# vco_main.net
KiCad netlist of a schematic drawn in EAGLE
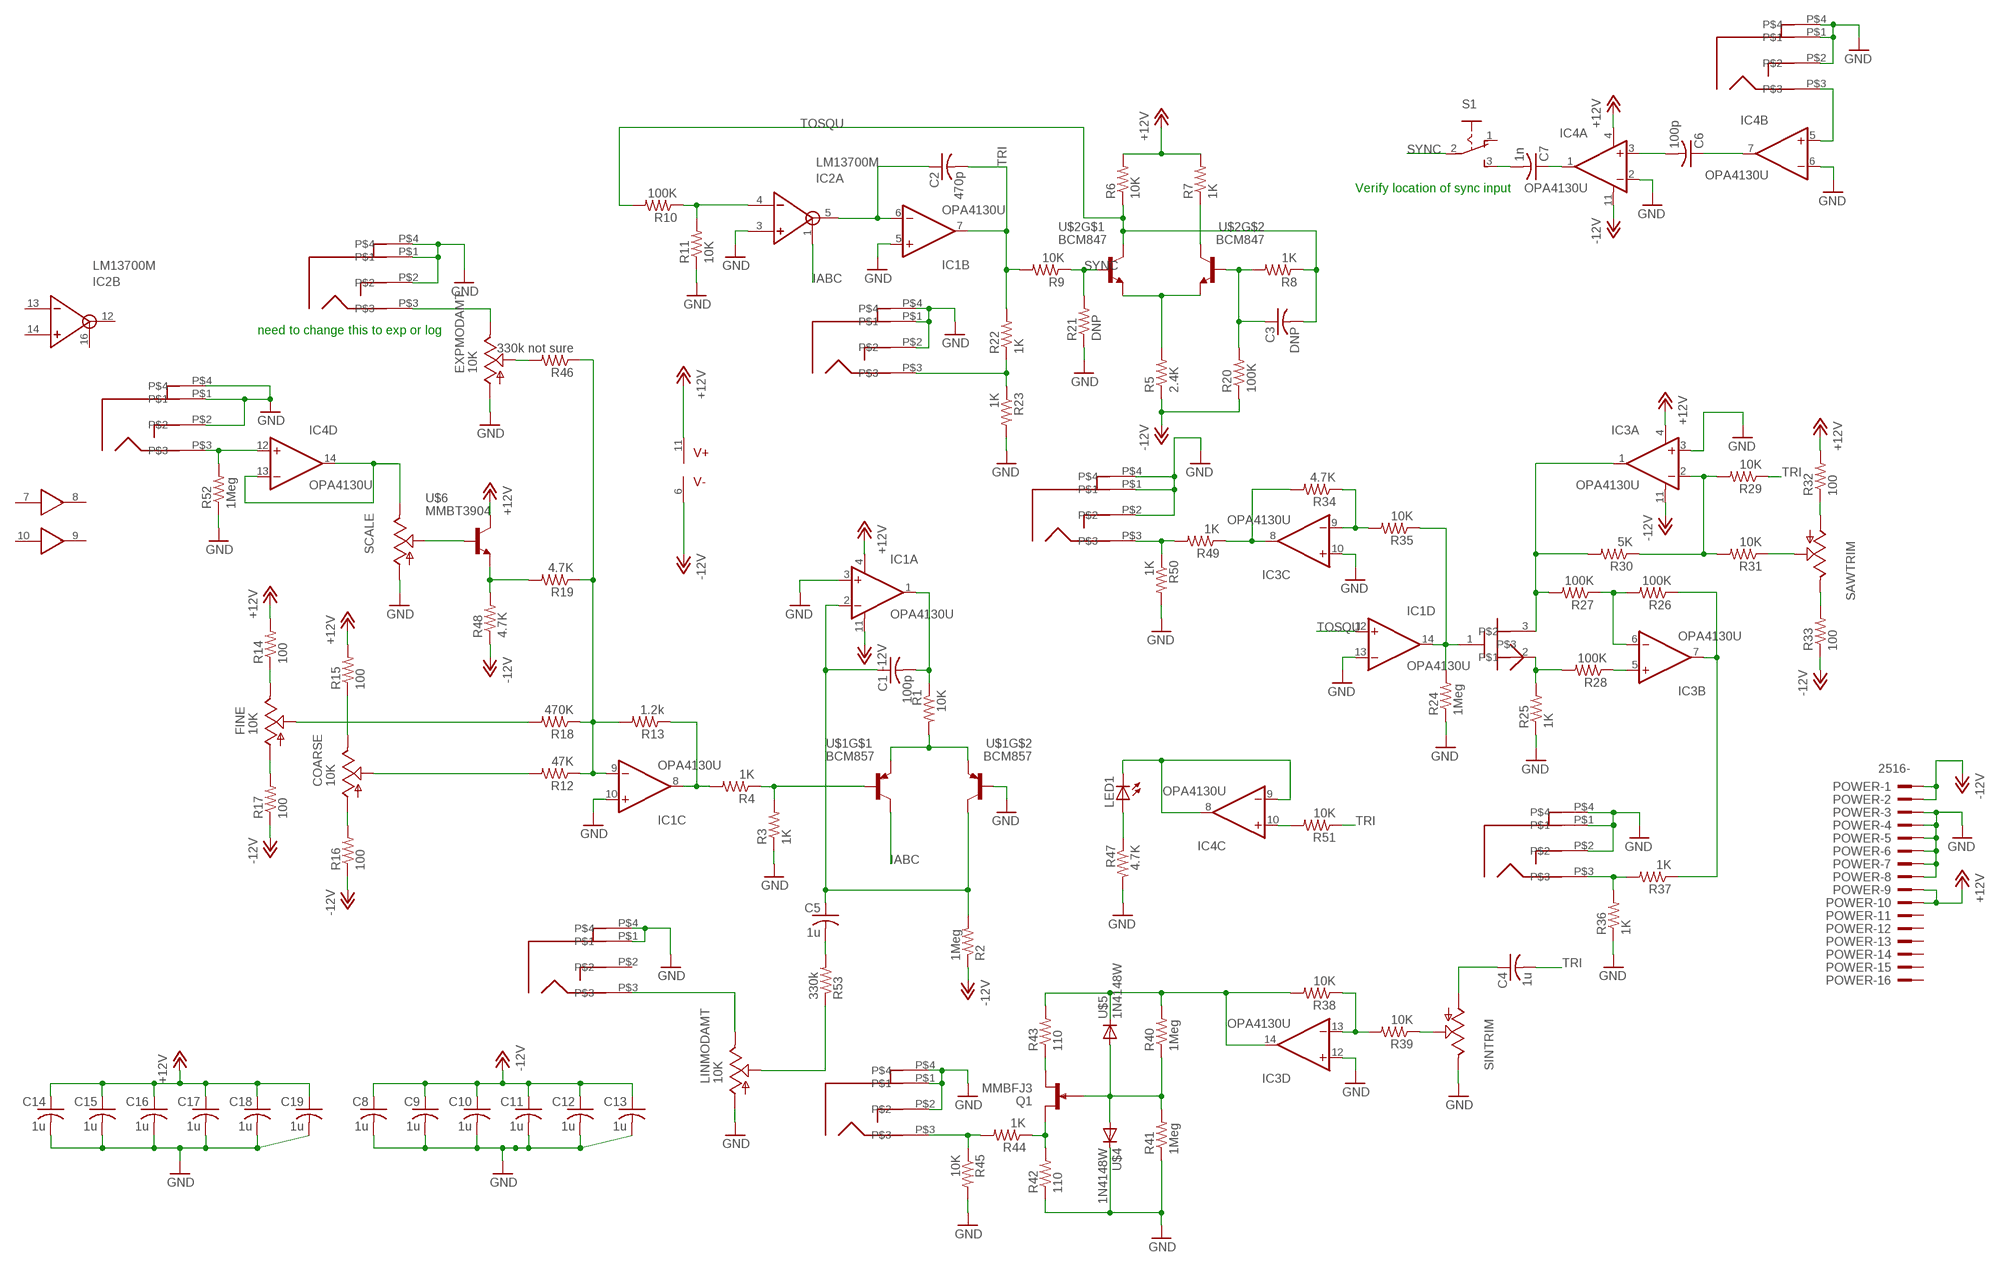
[diagram p0: schematic, sheet 1]

(export (version "E")
  (design (tool "Eeschema 10.0.6"))
  (components
    (comp (ref "C1")
      (value "100p")
      (footprint "eagle-import:C0603")
      (libsource (lib "eagle-import") (part "C-USC0603"))
    )
    (comp (ref "C2")
      (value "470p")
      (footprint "eagle-import:C0603")
      (libsource (lib "eagle-import") (part "C-USC0603"))
    )
    (comp (ref "C3")
      (value "DNP")
      (footprint "eagle-import:C0603")
      (libsource (lib "eagle-import") (part "C-USC0603"))
    )
    (comp (ref "C4")
      (value "1u")
      (footprint "eagle-import:C0603")
      (libsource (lib "eagle-import") (part "C-USC0603"))
    )
    (comp (ref "C5")
      (value "1u")
      (footprint "eagle-import:C0603")
      (libsource (lib "eagle-import") (part "C-USC0603"))
    )
    (comp (ref "C6")
      (value "100p")
      (footprint "eagle-import:C0603")
      (libsource (lib "eagle-import") (part "C-USC0603"))
    )
    (comp (ref "C7")
      (value "1n")
      (footprint "eagle-import:C0603")
      (libsource (lib "eagle-import") (part "C-USC0603"))
    )
    (comp (ref "C8")
      (value "1u")
      (footprint "eagle-import:C0603")
      (libsource (lib "eagle-import") (part "C-USC0603"))
    )
    (comp (ref "C9")
      (value "1u")
      (footprint "eagle-import:C0603")
      (libsource (lib "eagle-import") (part "C-USC0603"))
    )
    (comp (ref "C10")
      (value "1u")
      (footprint "eagle-import:C0603")
      (libsource (lib "eagle-import") (part "C-USC0603"))
    )
    (comp (ref "C11")
      (value "1u")
      (footprint "eagle-import:C0603")
      (libsource (lib "eagle-import") (part "C-USC0603"))
    )
    (comp (ref "C12")
      (value "1u")
      (footprint "eagle-import:C0603")
      (libsource (lib "eagle-import") (part "C-USC0603"))
    )
    (comp (ref "C13")
      (value "1u")
      (footprint "eagle-import:C0603")
      (libsource (lib "eagle-import") (part "C-USC0603"))
    )
    (comp (ref "C14")
      (value "1u")
      (footprint "eagle-import:C0603")
      (libsource (lib "eagle-import") (part "C-USC0603"))
    )
    (comp (ref "C15")
      (value "1u")
      (footprint "eagle-import:C0603")
      (libsource (lib "eagle-import") (part "C-USC0603"))
    )
    (comp (ref "C16")
      (value "1u")
      (footprint "eagle-import:C0603")
      (libsource (lib "eagle-import") (part "C-USC0603"))
    )
    (comp (ref "C17")
      (value "1u")
      (footprint "eagle-import:C0603")
      (libsource (lib "eagle-import") (part "C-USC0603"))
    )
    (comp (ref "C18")
      (value "1u")
      (footprint "eagle-import:C0603")
      (libsource (lib "eagle-import") (part "C-USC0603"))
    )
    (comp (ref "C19")
      (value "1u")
      (footprint "eagle-import:C0603")
      (libsource (lib "eagle-import") (part "C-USC0603"))
    )
    (comp (ref "COARSE")
      (value "10K")
      (footprint "eagle-import:EVUFXJ")
      (libsource (lib "eagle-import") (part "US-EVUF2J"))
    )
    (comp (ref "EXPMOD")
      (value "PJ301BM")
      (footprint "eagle-import:PJ301BM")
      (libsource (lib "eagle-import") (part "PJ301BM"))
    )
    (comp (ref "EXPMODAMT")
      (value "10K")
      (footprint "eagle-import:EVUFXJ")
      (libsource (lib "eagle-import") (part "US-EVUF2J"))
    )
    (comp (ref "FINE")
      (value "10K")
      (footprint "eagle-import:EVUFXJ")
      (libsource (lib "eagle-import") (part "US-EVUF2J"))
    )
    (comp (ref "IC1")
      (value "OPA4130U")
      (footprint "eagle-import:SO14")
      (fields (field (name "MF") "TEXAS INSTRUMENTS") (field (name "MPN") "OPA4130UA"))
      (libsource (lib "eagle-import") (part "OPA4130U"))
    )
    (comp (ref "IC2")
      (value "LM13700M")
      (footprint "eagle-import:SO16")
      (libsource (lib "eagle-import") (part "LM13700M"))
    )
    (comp (ref "IC3")
      (value "OPA4130U")
      (footprint "eagle-import:SO14")
      (fields (field (name "MF") "TEXAS INSTRUMENTS") (field (name "MPN") "OPA4130UA"))
      (libsource (lib "eagle-import") (part "OPA4130U"))
    )
    (comp (ref "IC4")
      (value "OPA4130U")
      (footprint "eagle-import:SO14")
      (fields (field (name "MF") "TEXAS INSTRUMENTS") (field (name "MPN") "OPA4130UA"))
      (libsource (lib "eagle-import") (part "OPA4130U"))
    )
    (comp (ref "LED1")
      (value "LED5MM")
      (footprint "eagle-import:LED5MM")
      (libsource (lib "eagle-import") (part "LED5MM"))
    )
    (comp (ref "LINMOD")
      (value "PJ301BM")
      (footprint "eagle-import:PJ301BM")
      (libsource (lib "eagle-import") (part "PJ301BM"))
    )
    (comp (ref "LINMODAMT")
      (value "10K")
      (footprint "eagle-import:EVUFXJ")
      (libsource (lib "eagle-import") (part "US-EVUF2J"))
    )
    (comp (ref "POWER")
      (value "2516-")
      (footprint "eagle-import:PAK100_2500-16")
      (libsource (lib "eagle-import") (part "2516-"))
    )
    (comp (ref "Q1")
      (value "MMBFJ3")
      (footprint "eagle-import:SOT23")
      (libsource (lib "eagle-import") (part "MMBFJ3"))
    )
    (comp (ref "R1")
      (value "10K")
      (footprint "eagle-import:R0603")
      (libsource (lib "eagle-import") (part "R-US_R0603"))
    )
    (comp (ref "R2")
      (value "1Meg")
      (footprint "eagle-import:R0603")
      (libsource (lib "eagle-import") (part "R-US_R0603"))
    )
    (comp (ref "R3")
      (value "1K")
      (footprint "eagle-import:R0603")
      (libsource (lib "eagle-import") (part "R-US_R0603"))
    )
    (comp (ref "R4")
      (value "1K")
      (footprint "eagle-import:R0603")
      (libsource (lib "eagle-import") (part "R-US_R0603"))
    )
    (comp (ref "R5")
      (value "2.4K")
      (footprint "eagle-import:R0603")
      (libsource (lib "eagle-import") (part "R-US_R0603"))
    )
    (comp (ref "R6")
      (value "10K")
      (footprint "eagle-import:R0603")
      (libsource (lib "eagle-import") (part "R-US_R0603"))
    )
    (comp (ref "R7")
      (value "1K")
      (footprint "eagle-import:R0603")
      (libsource (lib "eagle-import") (part "R-US_R0603"))
    )
    (comp (ref "R8")
      (value "1K")
      (footprint "eagle-import:R0603")
      (libsource (lib "eagle-import") (part "R-US_R0603"))
    )
    (comp (ref "R9")
      (value "10K")
      (footprint "eagle-import:R0603")
      (libsource (lib "eagle-import") (part "R-US_R0603"))
    )
    (comp (ref "R10")
      (value "100K")
      (footprint "eagle-import:R0603")
      (libsource (lib "eagle-import") (part "R-US_R0603"))
    )
    (comp (ref "R11")
      (value "10K")
      (footprint "eagle-import:R0603")
      (libsource (lib "eagle-import") (part "R-US_R0603"))
    )
    (comp (ref "R12")
      (value "47K")
      (footprint "eagle-import:R0603")
      (libsource (lib "eagle-import") (part "R-US_R0603"))
    )
    (comp (ref "R13")
      (value "1.2k")
      (footprint "eagle-import:R0603")
      (libsource (lib "eagle-import") (part "R-US_R0603"))
    )
    (comp (ref "R14")
      (value "100")
      (footprint "eagle-import:R0603")
      (libsource (lib "eagle-import") (part "R-US_R0603"))
    )
    (comp (ref "R15")
      (value "100")
      (footprint "eagle-import:R0603")
      (libsource (lib "eagle-import") (part "R-US_R0603"))
    )
    (comp (ref "R16")
      (value "100")
      (footprint "eagle-import:R0603")
      (libsource (lib "eagle-import") (part "R-US_R0603"))
    )
    (comp (ref "R17")
      (value "100")
      (footprint "eagle-import:R0603")
      (libsource (lib "eagle-import") (part "R-US_R0603"))
    )
    (comp (ref "R18")
      (value "470K")
      (footprint "eagle-import:R0603")
      (libsource (lib "eagle-import") (part "R-US_R0603"))
    )
    (comp (ref "R19")
      (value "4.7K")
      (footprint "eagle-import:R0603")
      (libsource (lib "eagle-import") (part "R-US_R0603"))
    )
    (comp (ref "R20")
      (value "100K")
      (footprint "eagle-import:R0603")
      (libsource (lib "eagle-import") (part "R-US_R0603"))
    )
    (comp (ref "R21")
      (value "DNP")
      (footprint "eagle-import:R0603")
      (libsource (lib "eagle-import") (part "R-US_R0603"))
    )
    (comp (ref "R22")
      (value "1K")
      (footprint "eagle-import:R0603")
      (libsource (lib "eagle-import") (part "R-US_R0603"))
    )
    (comp (ref "R23")
      (value "1K")
      (footprint "eagle-import:R0603")
      (libsource (lib "eagle-import") (part "R-US_R0603"))
    )
    (comp (ref "R24")
      (value "1Meg")
      (footprint "eagle-import:R0603")
      (libsource (lib "eagle-import") (part "R-US_R0603"))
    )
    (comp (ref "R25")
      (value "1K")
      (footprint "eagle-import:R0603")
      (libsource (lib "eagle-import") (part "R-US_R0603"))
    )
    (comp (ref "R26")
      (value "100K")
      (footprint "eagle-import:R0603")
      (libsource (lib "eagle-import") (part "R-US_R0603"))
    )
    (comp (ref "R27")
      (value "100K")
      (footprint "eagle-import:R0603")
      (libsource (lib "eagle-import") (part "R-US_R0603"))
    )
    (comp (ref "R28")
      (value "100K")
      (footprint "eagle-import:R0603")
      (libsource (lib "eagle-import") (part "R-US_R0603"))
    )
    (comp (ref "R29")
      (value "10K")
      (footprint "eagle-import:R0603")
      (libsource (lib "eagle-import") (part "R-US_R0603"))
    )
    (comp (ref "R30")
      (value "5K")
      (footprint "eagle-import:R0603")
      (libsource (lib "eagle-import") (part "R-US_R0603"))
    )
    (comp (ref "R31")
      (value "10K")
      (footprint "eagle-import:R0603")
      (libsource (lib "eagle-import") (part "R-US_R0603"))
    )
    (comp (ref "R32")
      (value "100")
      (footprint "eagle-import:R0603")
      (libsource (lib "eagle-import") (part "R-US_R0603"))
    )
    (comp (ref "R33")
      (value "100")
      (footprint "eagle-import:R0603")
      (libsource (lib "eagle-import") (part "R-US_R0603"))
    )
    (comp (ref "R34")
      (value "4.7K")
      (footprint "eagle-import:R0603")
      (libsource (lib "eagle-import") (part "R-US_R0603"))
    )
    (comp (ref "R35")
      (value "10K")
      (footprint "eagle-import:R0603")
      (libsource (lib "eagle-import") (part "R-US_R0603"))
    )
    (comp (ref "R36")
      (value "1K")
      (footprint "eagle-import:R0603")
      (libsource (lib "eagle-import") (part "R-US_R0603"))
    )
    (comp (ref "R37")
      (value "1K")
      (footprint "eagle-import:R0603")
      (libsource (lib "eagle-import") (part "R-US_R0603"))
    )
    (comp (ref "R38")
      (value "10K")
      (footprint "eagle-import:R0603")
      (libsource (lib "eagle-import") (part "R-US_R0603"))
    )
    (comp (ref "R39")
      (value "10K")
      (footprint "eagle-import:R0603")
      (libsource (lib "eagle-import") (part "R-US_R0603"))
    )
    (comp (ref "R40")
      (value "1Meg")
      (footprint "eagle-import:R0603")
      (libsource (lib "eagle-import") (part "R-US_R0603"))
    )
    (comp (ref "R41")
      (value "1Meg")
      (footprint "eagle-import:R0603")
      (libsource (lib "eagle-import") (part "R-US_R0603"))
    )
    (comp (ref "R42")
      (value "110")
      (footprint "eagle-import:R0603")
      (libsource (lib "eagle-import") (part "R-US_R0603"))
    )
    (comp (ref "R43")
      (value "110")
      (footprint "eagle-import:R0603")
      (libsource (lib "eagle-import") (part "R-US_R0603"))
    )
    (comp (ref "R44")
      (value "1K")
      (footprint "eagle-import:R0603")
      (libsource (lib "eagle-import") (part "R-US_R0603"))
    )
    (comp (ref "R45")
      (value "10K")
      (footprint "eagle-import:R0603")
      (libsource (lib "eagle-import") (part "R-US_R0603"))
    )
    (comp (ref "R46")
      (value "330k not sure")
      (footprint "eagle-import:R0603")
      (libsource (lib "eagle-import") (part "R-US_R0603"))
    )
    (comp (ref "R47")
      (value "4.7K")
      (footprint "eagle-import:R0603")
      (libsource (lib "eagle-import") (part "R-US_R0603"))
    )
    (comp (ref "R48")
      (value "4.7K")
      (footprint "eagle-import:R0603")
      (libsource (lib "eagle-import") (part "R-US_R0603"))
    )
    (comp (ref "R49")
      (value "1K")
      (footprint "eagle-import:R0603")
      (libsource (lib "eagle-import") (part "R-US_R0603"))
    )
    (comp (ref "R50")
      (value "1K")
      (footprint "eagle-import:R0603")
      (libsource (lib "eagle-import") (part "R-US_R0603"))
    )
    (comp (ref "R51")
      (value "10K")
      (footprint "eagle-import:R0603")
      (libsource (lib "eagle-import") (part "R-US_R0603"))
    )
    (comp (ref "R52")
      (value "1Meg")
      (footprint "eagle-import:R0603")
      (libsource (lib "eagle-import") (part "R-US_R0603"))
    )
    (comp (ref "R53")
      (value "330k")
      (footprint "eagle-import:R0603")
      (libsource (lib "eagle-import") (part "R-US_R0603"))
    )
    (comp (ref "S1")
      (value "255SB")
      (footprint "eagle-import:255SB")
      (libsource (lib "eagle-import") (part "255SB"))
    )
    (comp (ref "SAW")
      (value "PJ301BM")
      (footprint "eagle-import:PJ301BM")
      (libsource (lib "eagle-import") (part "PJ301BM"))
    )
    (comp (ref "SAWTRIM")
      (value "TRIM_US-B64Y")
      (footprint "eagle-import:B64Y")
      (libsource (lib "eagle-import") (part "TRIM_US-B64Y"))
    )
    (comp (ref "SCALE")
      (value "TRIM_US-B64Y")
      (footprint "eagle-import:B64Y")
      (libsource (lib "eagle-import") (part "TRIM_US-B64Y"))
    )
    (comp (ref "SIN")
      (value "PJ301BM")
      (footprint "eagle-import:PJ301BM")
      (libsource (lib "eagle-import") (part "PJ301BM"))
    )
    (comp (ref "SINTRIM")
      (value "TRIM_US-B64Y")
      (footprint "eagle-import:B64Y")
      (libsource (lib "eagle-import") (part "TRIM_US-B64Y"))
    )
    (comp (ref "SQUARE")
      (value "PJ301BM")
      (footprint "eagle-import:PJ301BM")
      (libsource (lib "eagle-import") (part "PJ301BM"))
    )
    (comp (ref "SYNC")
      (value "PJ301BM")
      (footprint "eagle-import:PJ301BM")
      (libsource (lib "eagle-import") (part "PJ301BM"))
    )
    (comp (ref "TRIOUT")
      (value "PJ301BM")
      (footprint "eagle-import:PJ301BM")
      (libsource (lib "eagle-import") (part "PJ301BM"))
    )
    (comp (ref "U$1")
      (value "BCM857")
      (footprint "eagle-import:SOT457R_PHILIPS")
      (libsource (lib "eagle-import") (part "BCM857"))
    )
    (comp (ref "U$2")
      (value "BCM847")
      (footprint "eagle-import:SOT457R_PHILIPS")
      (libsource (lib "eagle-import") (part "BCM847"))
    )
    (comp (ref "U$3")
      (value "2N7000")
      (footprint "eagle-import:SOT23")
      (libsource (lib "eagle-import") (part "2N7000"))
    )
    (comp (ref "U$4")
      (value "1N4148W")
      (footprint "eagle-import:SOD123")
      (libsource (lib "eagle-import") (part "1N4148W"))
    )
    (comp (ref "U$5")
      (value "1N4148W")
      (footprint "eagle-import:SOD123")
      (libsource (lib "eagle-import") (part "1N4148W"))
    )
    (comp (ref "U$6")
      (value "MMBT3904")
      (footprint "eagle-import:SOT23")
      (libsource (lib "eagle-import") (part "MMBT3904"))
    )
    (comp (ref "VPEROCT")
      (value "PJ301BM")
      (footprint "eagle-import:PJ301BM")
      (libsource (lib "eagle-import") (part "PJ301BM"))
    )
  )
  (nets
    (net (code "1") (name "+12V") (class "Default")
      (node (ref "C14") (pin "1") (pinfunction "1_1") (pintype "passive"))
      (node (ref "C15") (pin "1") (pinfunction "1_1") (pintype "passive"))
      (node (ref "C16") (pin "1") (pinfunction "1_1") (pintype "passive"))
      (node (ref "C17") (pin "1") (pinfunction "1_1") (pintype "passive"))
      (node (ref "C18") (pin "1") (pinfunction "1_1") (pintype "passive"))
      (node (ref "C19") (pin "1") (pinfunction "1_1") (pintype "passive"))
      (node (ref "IC1") (pin "4") (pinfunction "V+_4") (pintype "power_in"))
      (node (ref "IC2") (pin "11") (pinfunction "V+_11") (pintype "bidirectional"))
      (node (ref "IC3") (pin "4") (pinfunction "V+_4") (pintype "power_in"))
      (node (ref "IC4") (pin "4") (pinfunction "V+_4") (pintype "power_in"))
      (node (ref "POWER") (pin "10") (pinfunction "KL_10") (pintype "passive"))
      (node (ref "POWER") (pin "9") (pinfunction "KL_9") (pintype "passive"))
      (node (ref "R14") (pin "2") (pinfunction "2_2") (pintype "passive"))
      (node (ref "R15") (pin "2") (pinfunction "2_2") (pintype "passive"))
      (node (ref "R32") (pin "2") (pinfunction "2_2") (pintype "passive"))
      (node (ref "R6") (pin "2") (pinfunction "2_2") (pintype "passive"))
      (node (ref "R7") (pin "2") (pinfunction "2_2") (pintype "passive"))
      (node (ref "U$6") (pin "3") (pinfunction "C_3") (pintype "passive"))
    )
    (net (code "2") (name "-12V") (class "Default")
      (node (ref "C10") (pin "1") (pinfunction "1_1") (pintype "passive"))
      (node (ref "C11") (pin "1") (pinfunction "1_1") (pintype "passive"))
      (node (ref "C12") (pin "1") (pinfunction "1_1") (pintype "passive"))
      (node (ref "C13") (pin "1") (pinfunction "1_1") (pintype "passive"))
      (node (ref "C8") (pin "1") (pinfunction "1_1") (pintype "passive"))
      (node (ref "C9") (pin "1") (pinfunction "1_1") (pintype "passive"))
      (node (ref "IC1") (pin "11") (pinfunction "V-_11") (pintype "power_in"))
      (node (ref "IC2") (pin "6") (pinfunction "V-_6") (pintype "bidirectional"))
      (node (ref "IC3") (pin "11") (pinfunction "V-_11") (pintype "power_in"))
      (node (ref "IC4") (pin "11") (pinfunction "V-_11") (pintype "power_in"))
      (node (ref "POWER") (pin "1") (pinfunction "KL_1") (pintype "passive"))
      (node (ref "POWER") (pin "2") (pinfunction "KL_2") (pintype "passive"))
      (node (ref "R16") (pin "1") (pinfunction "1_1") (pintype "passive"))
      (node (ref "R17") (pin "1") (pinfunction "1_1") (pintype "passive"))
      (node (ref "R2") (pin "1") (pinfunction "1_1") (pintype "passive"))
      (node (ref "R20") (pin "1") (pinfunction "1_1") (pintype "passive"))
      (node (ref "R33") (pin "1") (pinfunction "1_1") (pintype "passive"))
      (node (ref "R48") (pin "1") (pinfunction "1_1") (pintype "passive"))
      (node (ref "R5") (pin "1") (pinfunction "1_1") (pintype "passive"))
    )
    (net (code "3") (name "/IABC") (class "Default")
      (node (ref "IC2") (pin "1") (pinfunction "IABC_1") (pintype "bidirectional"))
      (node (ref "U$1") (pin "6") (pinfunction "C_6") (pintype "passive"))
    )
    (net (code "4") (name "/SYNC") (class "Default")
      (node (ref "R21") (pin "2") (pinfunction "2_2") (pintype "passive"))
      (node (ref "R9") (pin "1") (pinfunction "1_1") (pintype "passive"))
      (node (ref "S1") (pin "2") (pinfunction "P_2") (pintype "passive"))
      (node (ref "U$2") (pin "2") (pinfunction "B_2") (pintype "passive"))
    )
    (net (code "5") (name "/TOSQU") (class "Default")
      (node (ref "C3") (pin "2") (pinfunction "2_2") (pintype "passive"))
      (node (ref "IC1") (pin "12") (pinfunction "+IN_12") (pintype "input"))
      (node (ref "R10") (pin "2") (pinfunction "2_2") (pintype "passive"))
      (node (ref "R6") (pin "1") (pinfunction "1_1") (pintype "passive"))
      (node (ref "R8") (pin "1") (pinfunction "1_1") (pintype "passive"))
      (node (ref "U$2") (pin "6") (pinfunction "C_6") (pintype "passive"))
    )
    (net (code "6") (name "/TRI") (class "Default")
      (node (ref "C2") (pin "2") (pinfunction "2_2") (pintype "passive"))
      (node (ref "C4") (pin "2") (pinfunction "2_2") (pintype "passive"))
      (node (ref "IC1") (pin "7") (pinfunction "OUT_7") (pintype "output"))
      (node (ref "R22") (pin "2") (pinfunction "2_2") (pintype "passive"))
      (node (ref "R29") (pin "1") (pinfunction "1_1") (pintype "passive"))
      (node (ref "R51") (pin "1") (pinfunction "1_1") (pintype "passive"))
      (node (ref "R9") (pin "2") (pinfunction "2_2") (pintype "passive"))
    )
    (net (code "7") (name "GND") (class "Default")
      (node (ref "C10") (pin "2") (pinfunction "2_2") (pintype "passive"))
      (node (ref "C11") (pin "2") (pinfunction "2_2") (pintype "passive"))
      (node (ref "C12") (pin "2") (pinfunction "2_2") (pintype "passive"))
      (node (ref "C13") (pin "2") (pinfunction "2_2") (pintype "passive"))
      (node (ref "C14") (pin "2") (pinfunction "2_2") (pintype "passive"))
      (node (ref "C15") (pin "2") (pinfunction "2_2") (pintype "passive"))
      (node (ref "C16") (pin "2") (pinfunction "2_2") (pintype "passive"))
      (node (ref "C17") (pin "2") (pinfunction "2_2") (pintype "passive"))
      (node (ref "C18") (pin "2") (pinfunction "2_2") (pintype "passive"))
      (node (ref "C19") (pin "2") (pinfunction "2_2") (pintype "passive"))
      (node (ref "C8") (pin "2") (pinfunction "2_2") (pintype "passive"))
      (node (ref "C9") (pin "2") (pinfunction "2_2") (pintype "passive"))
      (node (ref "EXPMOD") (pin "P$1") (pinfunction "P$1_P$1") (pintype "bidirectional"))
      (node (ref "EXPMOD") (pin "P$2") (pinfunction "P$2_P$2") (pintype "bidirectional"))
      (node (ref "EXPMOD") (pin "P$4") (pinfunction "P$4_P$4") (pintype "bidirectional"))
      (node (ref "EXPMODAMT") (pin "1") (pinfunction "A_1") (pintype "passive"))
      (node (ref "IC1") (pin "10") (pinfunction "+IN_10") (pintype "input"))
      (node (ref "IC1") (pin "13") (pinfunction "-IN_13") (pintype "input"))
      (node (ref "IC1") (pin "3") (pinfunction "+IN_3") (pintype "input"))
      (node (ref "IC1") (pin "5") (pinfunction "+IN_5") (pintype "input"))
      (node (ref "IC2") (pin "3") (pinfunction "+IN_3") (pintype "bidirectional"))
      (node (ref "IC3") (pin "10") (pinfunction "+IN_10") (pintype "input"))
      (node (ref "IC3") (pin "12") (pinfunction "+IN_12") (pintype "input"))
      (node (ref "IC3") (pin "3") (pinfunction "+IN_3") (pintype "input"))
      (node (ref "IC4") (pin "2") (pinfunction "-IN_2") (pintype "input"))
      (node (ref "IC4") (pin "6") (pinfunction "-IN_6") (pintype "input"))
      (node (ref "LINMOD") (pin "P$1") (pinfunction "P$1_P$1") (pintype "bidirectional"))
      (node (ref "LINMOD") (pin "P$4") (pinfunction "P$4_P$4") (pintype "bidirectional"))
      (node (ref "LINMODAMT") (pin "1") (pinfunction "A_1") (pintype "passive"))
      (node (ref "POWER") (pin "3") (pinfunction "KL_3") (pintype "passive"))
      (node (ref "POWER") (pin "4") (pinfunction "KL_4") (pintype "passive"))
      (node (ref "POWER") (pin "5") (pinfunction "KL_5") (pintype "passive"))
      (node (ref "POWER") (pin "6") (pinfunction "KL_6") (pintype "passive"))
      (node (ref "POWER") (pin "7") (pinfunction "KL_7") (pintype "passive"))
      (node (ref "POWER") (pin "8") (pinfunction "KL_8") (pintype "passive"))
      (node (ref "R11") (pin "1") (pinfunction "1_1") (pintype "passive"))
      (node (ref "R21") (pin "1") (pinfunction "1_1") (pintype "passive"))
      (node (ref "R23") (pin "2") (pinfunction "2_2") (pintype "passive"))
      (node (ref "R24") (pin "1") (pinfunction "1_1") (pintype "passive"))
      (node (ref "R25") (pin "1") (pinfunction "1_1") (pintype "passive"))
      (node (ref "R3") (pin "1") (pinfunction "1_1") (pintype "passive"))
      (node (ref "R36") (pin "1") (pinfunction "1_1") (pintype "passive"))
      (node (ref "R41") (pin "1") (pinfunction "1_1") (pintype "passive"))
      (node (ref "R42") (pin "1") (pinfunction "1_1") (pintype "passive"))
      (node (ref "R45") (pin "2") (pinfunction "2_2") (pintype "passive"))
      (node (ref "R47") (pin "2") (pinfunction "2_2") (pintype "passive"))
      (node (ref "R50") (pin "2") (pinfunction "2_2") (pintype "passive"))
      (node (ref "R52") (pin "1") (pinfunction "1_1") (pintype "passive"))
      (node (ref "SAW") (pin "P$1") (pinfunction "P$1_P$1") (pintype "bidirectional"))
      (node (ref "SAW") (pin "P$2") (pinfunction "P$2_P$2") (pintype "bidirectional"))
      (node (ref "SAW") (pin "P$4") (pinfunction "P$4_P$4") (pintype "bidirectional"))
      (node (ref "SCALE") (pin "A") (pinfunction "A_A") (pintype "passive"))
      (node (ref "SIN") (pin "P$1") (pinfunction "P$1_P$1") (pintype "bidirectional"))
      (node (ref "SIN") (pin "P$2") (pinfunction "P$2_P$2") (pintype "bidirectional"))
      (node (ref "SIN") (pin "P$4") (pinfunction "P$4_P$4") (pintype "bidirectional"))
      (node (ref "SINTRIM") (pin "E") (pinfunction "E_E") (pintype "passive"))
      (node (ref "SQUARE") (pin "P$1") (pinfunction "P$1_P$1") (pintype "bidirectional"))
      (node (ref "SQUARE") (pin "P$2") (pinfunction "P$2_P$2") (pintype "bidirectional"))
      (node (ref "SQUARE") (pin "P$4") (pinfunction "P$4_P$4") (pintype "bidirectional"))
      (node (ref "SYNC") (pin "P$1") (pinfunction "P$1_P$1") (pintype "bidirectional"))
      (node (ref "SYNC") (pin "P$2") (pinfunction "P$2_P$2") (pintype "bidirectional"))
      (node (ref "SYNC") (pin "P$4") (pinfunction "P$4_P$4") (pintype "bidirectional"))
      (node (ref "TRIOUT") (pin "P$1") (pinfunction "P$1_P$1") (pintype "bidirectional"))
      (node (ref "TRIOUT") (pin "P$2") (pinfunction "P$2_P$2") (pintype "bidirectional"))
      (node (ref "TRIOUT") (pin "P$4") (pinfunction "P$4_P$4") (pintype "bidirectional"))
      (node (ref "U$1") (pin "5") (pinfunction "B_5") (pintype "passive"))
      (node (ref "U$4") (pin "C") (pinfunction "C_C") (pintype "passive"))
      (node (ref "VPEROCT") (pin "P$1") (pinfunction "P$1_P$1") (pintype "bidirectional"))
      (node (ref "VPEROCT") (pin "P$2") (pinfunction "P$2_P$2") (pintype "bidirectional"))
      (node (ref "VPEROCT") (pin "P$4") (pinfunction "P$4_P$4") (pintype "bidirectional"))
    )
    (net (code "8") (name "Net-(C4-Pad1)") (class "Default")
      (node (ref "C4") (pin "1") (pinfunction "1_1") (pintype "passive"))
      (node (ref "SINTRIM") (pin "A") (pinfunction "A_A") (pintype "passive"))
    )
    (net (code "9") (name "Net-(C5-Pad2)") (class "Default")
      (node (ref "C5") (pin "2") (pinfunction "2_2") (pintype "passive"))
      (node (ref "R53") (pin "2") (pinfunction "2_2") (pintype "passive"))
    )
    (net (code "10") (name "Net-(COARSE-A)") (class "Default")
      (node (ref "COARSE") (pin "1") (pinfunction "A_1") (pintype "passive"))
      (node (ref "R16") (pin "2") (pinfunction "2_2") (pintype "passive"))
    )
    (net (code "11") (name "Net-(COARSE-E)") (class "Default")
      (node (ref "COARSE") (pin "3") (pinfunction "E_3") (pintype "passive"))
      (node (ref "R15") (pin "1") (pinfunction "1_1") (pintype "passive"))
    )
    (net (code "12") (name "Net-(COARSE-S)") (class "Default")
      (node (ref "COARSE") (pin "2") (pinfunction "S_2") (pintype "passive"))
      (node (ref "R12") (pin "2") (pinfunction "2_2") (pintype "passive"))
    )
    (net (code "13") (name "Net-(EXPMODAMT-E)") (class "Default")
      (node (ref "EXPMOD") (pin "P$3") (pinfunction "P$3_P$3") (pintype "bidirectional"))
      (node (ref "EXPMODAMT") (pin "3") (pinfunction "E_3") (pintype "passive"))
    )
    (net (code "14") (name "Net-(EXPMODAMT-S)") (class "Default")
      (node (ref "EXPMODAMT") (pin "2") (pinfunction "S_2") (pintype "passive"))
      (node (ref "R46") (pin "2") (pinfunction "2_2") (pintype "passive"))
    )
    (net (code "15") (name "Net-(FINE-A)") (class "Default")
      (node (ref "FINE") (pin "1") (pinfunction "A_1") (pintype "passive"))
      (node (ref "R17") (pin "2") (pinfunction "2_2") (pintype "passive"))
    )
    (net (code "16") (name "Net-(FINE-E)") (class "Default")
      (node (ref "FINE") (pin "3") (pinfunction "E_3") (pintype "passive"))
      (node (ref "R14") (pin "1") (pinfunction "1_1") (pintype "passive"))
    )
    (net (code "17") (name "Net-(FINE-S)") (class "Default")
      (node (ref "FINE") (pin "2") (pinfunction "S_2") (pintype "passive"))
      (node (ref "R18") (pin "2") (pinfunction "2_2") (pintype "passive"))
    )
    (net (code "18") (name "Net-(IC1A--IN)") (class "Default")
      (node (ref "C1") (pin "1") (pinfunction "1_1") (pintype "passive"))
      (node (ref "C5") (pin "1") (pinfunction "1_1") (pintype "passive"))
      (node (ref "IC1") (pin "2") (pinfunction "-IN_2") (pintype "input"))
      (node (ref "R2") (pin "2") (pinfunction "2_2") (pintype "passive"))
      (node (ref "U$1") (pin "3") (pinfunction "C_3") (pintype "passive"))
    )
    (net (code "19") (name "Net-(IC1A-OUT)") (class "Default")
      (node (ref "C1") (pin "2") (pinfunction "2_2") (pintype "passive"))
      (node (ref "IC1") (pin "1") (pinfunction "OUT_1") (pintype "output"))
      (node (ref "R1") (pin "1") (pinfunction "1_1") (pintype "passive"))
    )
    (net (code "20") (name "Net-(IC1B--IN)") (class "Default")
      (node (ref "C2") (pin "1") (pinfunction "1_1") (pintype "passive"))
      (node (ref "IC1") (pin "6") (pinfunction "-IN_6") (pintype "input"))
      (node (ref "IC2") (pin "5") (pinfunction "OUT_5") (pintype "bidirectional"))
    )
    (net (code "21") (name "Net-(IC1C--IN)") (class "Default")
      (node (ref "IC1") (pin "9") (pinfunction "-IN_9") (pintype "input"))
      (node (ref "R12") (pin "1") (pinfunction "1_1") (pintype "passive"))
      (node (ref "R13") (pin "2") (pinfunction "2_2") (pintype "passive"))
      (node (ref "R18") (pin "1") (pinfunction "1_1") (pintype "passive"))
      (node (ref "R19") (pin "1") (pinfunction "1_1") (pintype "passive"))
      (node (ref "R46") (pin "1") (pinfunction "1_1") (pintype "passive"))
    )
    (net (code "22") (name "Net-(IC1C-OUT)") (class "Default")
      (node (ref "IC1") (pin "8") (pinfunction "OUT_8") (pintype "output"))
      (node (ref "R13") (pin "1") (pinfunction "1_1") (pintype "passive"))
      (node (ref "R4") (pin "2") (pinfunction "2_2") (pintype "passive"))
    )
    (net (code "23") (name "Net-(IC1D-OUT)") (class "Default")
      (node (ref "IC1") (pin "14") (pinfunction "OUT_14") (pintype "output"))
      (node (ref "R24") (pin "2") (pinfunction "2_2") (pintype "passive"))
      (node (ref "R35") (pin "1") (pinfunction "1_1") (pintype "passive"))
      (node (ref "U$3") (pin "1") (pinfunction "P$3_1") (pintype "bidirectional"))
    )
    (net (code "24") (name "Net-(IC2A--IN)") (class "Default")
      (node (ref "IC2") (pin "4") (pinfunction "-IN_4") (pintype "bidirectional"))
      (node (ref "R10") (pin "1") (pinfunction "1_1") (pintype "passive"))
      (node (ref "R11") (pin "2") (pinfunction "2_2") (pintype "passive"))
    )
    (net (code "25") (name "Net-(IC3A--IN)") (class "Default")
      (node (ref "IC3") (pin "2") (pinfunction "-IN_2") (pintype "input"))
      (node (ref "R29") (pin "2") (pinfunction "2_2") (pintype "passive"))
      (node (ref "R30") (pin "1") (pinfunction "1_1") (pintype "passive"))
      (node (ref "R31") (pin "2") (pinfunction "2_2") (pintype "passive"))
    )
    (net (code "26") (name "Net-(IC3A-OUT)") (class "Default")
      (node (ref "IC3") (pin "1") (pinfunction "OUT_1") (pintype "output"))
      (node (ref "R27") (pin "2") (pinfunction "2_2") (pintype "passive"))
      (node (ref "R30") (pin "2") (pinfunction "2_2") (pintype "passive"))
      (node (ref "U$3") (pin "3") (pinfunction "P$2_3") (pintype "bidirectional"))
    )
    (net (code "27") (name "Net-(IC3B-+IN)") (class "Default")
      (node (ref "IC3") (pin "5") (pinfunction "+IN_5") (pintype "input"))
      (node (ref "R28") (pin "1") (pinfunction "1_1") (pintype "passive"))
    )
    (net (code "28") (name "Net-(IC3B--IN)") (class "Default")
      (node (ref "IC3") (pin "6") (pinfunction "-IN_6") (pintype "input"))
      (node (ref "R26") (pin "2") (pinfunction "2_2") (pintype "passive"))
      (node (ref "R27") (pin "1") (pinfunction "1_1") (pintype "passive"))
    )
    (net (code "29") (name "Net-(IC3B-OUT)") (class "Default")
      (node (ref "IC3") (pin "7") (pinfunction "OUT_7") (pintype "output"))
      (node (ref "R26") (pin "1") (pinfunction "1_1") (pintype "passive"))
      (node (ref "R37") (pin "1") (pinfunction "1_1") (pintype "passive"))
    )
    (net (code "30") (name "Net-(IC3C--IN)") (class "Default")
      (node (ref "IC3") (pin "9") (pinfunction "-IN_9") (pintype "input"))
      (node (ref "R34") (pin "1") (pinfunction "1_1") (pintype "passive"))
      (node (ref "R35") (pin "2") (pinfunction "2_2") (pintype "passive"))
    )
    (net (code "31") (name "Net-(IC3C-OUT)") (class "Default")
      (node (ref "IC3") (pin "8") (pinfunction "OUT_8") (pintype "output"))
      (node (ref "R34") (pin "2") (pinfunction "2_2") (pintype "passive"))
      (node (ref "R49") (pin "1") (pinfunction "1_1") (pintype "passive"))
    )
    (net (code "32") (name "Net-(IC3D--IN)") (class "Default")
      (node (ref "IC3") (pin "13") (pinfunction "-IN_13") (pintype "input"))
      (node (ref "R38") (pin "1") (pinfunction "1_1") (pintype "passive"))
      (node (ref "R39") (pin "2") (pinfunction "2_2") (pintype "passive"))
    )
    (net (code "33") (name "Net-(IC3D-OUT)") (class "Default")
      (node (ref "IC3") (pin "14") (pinfunction "OUT_14") (pintype "output"))
      (node (ref "R38") (pin "2") (pinfunction "2_2") (pintype "passive"))
      (node (ref "R40") (pin "2") (pinfunction "2_2") (pintype "passive"))
      (node (ref "R43") (pin "2") (pinfunction "2_2") (pintype "passive"))
      (node (ref "U$5") (pin "C") (pinfunction "C_C") (pintype "passive"))
    )
    (net (code "34") (name "Net-(IC4A-+IN)") (class "Default")
      (node (ref "C6") (pin "2") (pinfunction "2_2") (pintype "passive"))
      (node (ref "IC4") (pin "3") (pinfunction "+IN_3") (pintype "input"))
    )
    (net (code "35") (name "Net-(IC4A-OUT)") (class "Default")
      (node (ref "C7") (pin "1") (pinfunction "1_1") (pintype "passive"))
      (node (ref "IC4") (pin "1") (pinfunction "OUT_1") (pintype "output"))
    )
    (net (code "36") (name "Net-(IC4B-+IN)") (class "Default")
      (node (ref "IC4") (pin "5") (pinfunction "+IN_5") (pintype "input"))
      (node (ref "SYNC") (pin "P$3") (pinfunction "P$3_P$3") (pintype "bidirectional"))
    )
    (net (code "37") (name "Net-(IC4B-OUT)") (class "Default")
      (node (ref "C6") (pin "1") (pinfunction "1_1") (pintype "passive"))
      (node (ref "IC4") (pin "7") (pinfunction "OUT_7") (pintype "output"))
    )
    (net (code "38") (name "Net-(IC4C-+IN)") (class "Default")
      (node (ref "IC4") (pin "10") (pinfunction "+IN_10") (pintype "input"))
      (node (ref "R51") (pin "2") (pinfunction "2_2") (pintype "passive"))
    )
    (net (code "39") (name "Net-(IC4C--IN)") (class "Default")
      (node (ref "IC4") (pin "8") (pinfunction "OUT_8") (pintype "output"))
      (node (ref "IC4") (pin "9") (pinfunction "-IN_9") (pintype "input"))
      (node (ref "LED1") (pin "K") (pinfunction "C_K") (pintype "passive"))
    )
    (net (code "40") (name "Net-(IC4D-+IN)") (class "Default")
      (node (ref "IC4") (pin "12") (pinfunction "+IN_12") (pintype "input"))
      (node (ref "R52") (pin "2") (pinfunction "2_2") (pintype "passive"))
      (node (ref "VPEROCT") (pin "P$3") (pinfunction "P$3_P$3") (pintype "bidirectional"))
    )
    (net (code "41") (name "Net-(IC4D--IN)") (class "Default")
      (node (ref "IC4") (pin "13") (pinfunction "-IN_13") (pintype "input"))
      (node (ref "IC4") (pin "14") (pinfunction "OUT_14") (pintype "output"))
      (node (ref "SCALE") (pin "E") (pinfunction "E_E") (pintype "passive"))
    )
    (net (code "42") (name "Net-(LED1-PadA)") (class "Default")
      (node (ref "LED1") (pin "A") (pinfunction "A_A") (pintype "passive"))
      (node (ref "R47") (pin "1") (pinfunction "1_1") (pintype "passive"))
    )
    (net (code "43") (name "Net-(LINMODAMT-E)") (class "Default")
      (node (ref "LINMOD") (pin "P$3") (pinfunction "P$3_P$3") (pintype "bidirectional"))
      (node (ref "LINMODAMT") (pin "3") (pinfunction "E_3") (pintype "passive"))
    )
    (net (code "44") (name "Net-(LINMODAMT-S)") (class "Default")
      (node (ref "LINMODAMT") (pin "2") (pinfunction "S_2") (pintype "passive"))
      (node (ref "R53") (pin "1") (pinfunction "1_1") (pintype "passive"))
    )
    (net (code "45") (name "Net-(Q1-D)") (class "Default")
      (node (ref "Q1") (pin "1") (pinfunction "D_1") (pintype "passive"))
      (node (ref "R42") (pin "2") (pinfunction "2_2") (pintype "passive"))
      (node (ref "R44") (pin "1") (pinfunction "1_1") (pintype "passive"))
    )
    (net (code "46") (name "Net-(Q1-G)") (class "Default")
      (node (ref "Q1") (pin "3") (pinfunction "G_3") (pintype "passive"))
      (node (ref "R40") (pin "1") (pinfunction "1_1") (pintype "passive"))
      (node (ref "R41") (pin "2") (pinfunction "2_2") (pintype "passive"))
      (node (ref "U$4") (pin "A") (pinfunction "A_A") (pintype "passive"))
      (node (ref "U$5") (pin "A") (pinfunction "A_A") (pintype "passive"))
    )
    (net (code "47") (name "Net-(Q1-S)") (class "Default")
      (node (ref "Q1") (pin "2") (pinfunction "S_2") (pintype "passive"))
      (node (ref "R43") (pin "1") (pinfunction "1_1") (pintype "passive"))
    )
    (net (code "48") (name "Net-(R22-Pad1)") (class "Default")
      (node (ref "R22") (pin "1") (pinfunction "1_1") (pintype "passive"))
      (node (ref "R23") (pin "1") (pinfunction "1_1") (pintype "passive"))
      (node (ref "TRIOUT") (pin "P$3") (pinfunction "P$3_P$3") (pintype "bidirectional"))
    )
    (net (code "49") (name "Net-(R31-Pad1)") (class "Default")
      (node (ref "R31") (pin "1") (pinfunction "1_1") (pintype "passive"))
      (node (ref "SAWTRIM") (pin "S") (pinfunction "S_S") (pintype "passive"))
    )
    (net (code "50") (name "Net-(R32-Pad1)") (class "Default")
      (node (ref "R32") (pin "1") (pinfunction "1_1") (pintype "passive"))
      (node (ref "SAWTRIM") (pin "A") (pinfunction "A_A") (pintype "passive"))
    )
    (net (code "51") (name "Net-(R33-Pad2)") (class "Default")
      (node (ref "R33") (pin "2") (pinfunction "2_2") (pintype "passive"))
      (node (ref "SAWTRIM") (pin "E") (pinfunction "E_E") (pintype "passive"))
    )
    (net (code "52") (name "Net-(R36-Pad2)") (class "Default")
      (node (ref "R36") (pin "2") (pinfunction "2_2") (pintype "passive"))
      (node (ref "R37") (pin "2") (pinfunction "2_2") (pintype "passive"))
      (node (ref "SAW") (pin "P$3") (pinfunction "P$3_P$3") (pintype "bidirectional"))
    )
    (net (code "53") (name "Net-(R39-Pad1)") (class "Default")
      (node (ref "R39") (pin "1") (pinfunction "1_1") (pintype "passive"))
      (node (ref "SINTRIM") (pin "S") (pinfunction "S_S") (pintype "passive"))
    )
    (net (code "54") (name "Net-(R44-Pad2)") (class "Default")
      (node (ref "R44") (pin "2") (pinfunction "2_2") (pintype "passive"))
      (node (ref "R45") (pin "1") (pinfunction "1_1") (pintype "passive"))
      (node (ref "SIN") (pin "P$3") (pinfunction "P$3_P$3") (pintype "bidirectional"))
    )
    (net (code "55") (name "Net-(R49-Pad2)") (class "Default")
      (node (ref "R49") (pin "2") (pinfunction "2_2") (pintype "passive"))
      (node (ref "R50") (pin "1") (pinfunction "1_1") (pintype "passive"))
      (node (ref "SQUARE") (pin "P$3") (pinfunction "P$3_P$3") (pintype "bidirectional"))
    )
    (net (code "56") (name "Net-(S1-S)") (class "Default")
      (node (ref "C7") (pin "2") (pinfunction "2_2") (pintype "passive"))
      (node (ref "S1") (pin "3") (pinfunction "S_3") (pintype "passive"))
    )
    (net (code "57") (name "Net-(U$1A-B)") (class "Default")
      (node (ref "R3") (pin "2") (pinfunction "2_2") (pintype "passive"))
      (node (ref "R4") (pin "1") (pinfunction "1_1") (pintype "passive"))
      (node (ref "U$1") (pin "2") (pinfunction "B_2") (pintype "passive"))
    )
    (net (code "58") (name "Net-(U$1A-E)") (class "Default")
      (node (ref "R1") (pin "2") (pinfunction "2_2") (pintype "passive"))
      (node (ref "U$1") (pin "1") (pinfunction "E_1") (pintype "passive"))
      (node (ref "U$1") (pin "4") (pinfunction "E_4") (pintype "passive"))
    )
    (net (code "59") (name "Net-(U$2A-E)") (class "Default")
      (node (ref "R5") (pin "2") (pinfunction "2_2") (pintype "passive"))
      (node (ref "U$2") (pin "1") (pinfunction "E_1") (pintype "passive"))
      (node (ref "U$2") (pin "4") (pinfunction "E_4") (pintype "passive"))
    )
    (net (code "60") (name "Net-(U$2B-B)") (class "Default")
      (node (ref "C3") (pin "1") (pinfunction "1_1") (pintype "passive"))
      (node (ref "R20") (pin "2") (pinfunction "2_2") (pintype "passive"))
      (node (ref "R8") (pin "2") (pinfunction "2_2") (pintype "passive"))
      (node (ref "U$2") (pin "5") (pinfunction "B_5") (pintype "passive"))
    )
    (net (code "61") (name "Net-(U$2B-C)") (class "Default")
      (node (ref "R7") (pin "1") (pinfunction "1_1") (pintype "passive"))
      (node (ref "U$2") (pin "3") (pinfunction "C_3") (pintype "passive"))
    )
    (net (code "62") (name "Net-(U$3-P$1)") (class "Default")
      (node (ref "R25") (pin "2") (pinfunction "2_2") (pintype "passive"))
      (node (ref "R28") (pin "2") (pinfunction "2_2") (pintype "passive"))
      (node (ref "U$3") (pin "2") (pinfunction "P$1_2") (pintype "bidirectional"))
    )
    (net (code "63") (name "Net-(U$6-B)") (class "Default")
      (node (ref "SCALE") (pin "S") (pinfunction "S_S") (pintype "passive"))
      (node (ref "U$6") (pin "1") (pinfunction "B_1") (pintype "passive"))
    )
    (net (code "64") (name "Net-(U$6-E)") (class "Default")
      (node (ref "R19") (pin "2") (pinfunction "2_2") (pintype "passive"))
      (node (ref "R48") (pin "2") (pinfunction "2_2") (pintype "passive"))
      (node (ref "U$6") (pin "2") (pinfunction "E_2") (pintype "passive"))
    )
    (net (code "65") (name "unconnected-(IC2B-+IN-Pad14)") (class "Default")
      (node (ref "IC2") (pin "14") (pinfunction "+IN_14") (pintype "bidirectional"))
    )
    (net (code "66") (name "unconnected-(IC2B--IN-Pad13)") (class "Default")
      (node (ref "IC2") (pin "13") (pinfunction "-IN_13") (pintype "bidirectional"))
    )
    (net (code "67") (name "unconnected-(IC2B-IABC-Pad16)") (class "Default")
      (node (ref "IC2") (pin "16") (pinfunction "IABC_16") (pintype "bidirectional"))
    )
    (net (code "68") (name "unconnected-(IC2B-OUT-Pad12)") (class "Default")
      (node (ref "IC2") (pin "12") (pinfunction "OUT_12") (pintype "bidirectional"))
    )
    (net (code "69") (name "unconnected-(IC2C-IN-Pad7)") (class "Default")
      (node (ref "IC2") (pin "7") (pinfunction "IN_7") (pintype "bidirectional"))
    )
    (net (code "70") (name "unconnected-(IC2C-OUT-Pad8)") (class "Default")
      (node (ref "IC2") (pin "8") (pinfunction "OUT_8") (pintype "bidirectional"))
    )
    (net (code "71") (name "unconnected-(IC2D-IN-Pad10)") (class "Default")
      (node (ref "IC2") (pin "10") (pinfunction "IN_10") (pintype "bidirectional"))
    )
    (net (code "72") (name "unconnected-(IC2D-OUT-Pad9)") (class "Default")
      (node (ref "IC2") (pin "9") (pinfunction "OUT_9") (pintype "bidirectional"))
    )
    (net (code "73") (name "unconnected-(LINMOD-PadP$2)") (class "Default")
      (node (ref "LINMOD") (pin "P$2") (pinfunction "P$2_P$2") (pintype "bidirectional"))
    )
    (net (code "74") (name "unconnected-(POWERC-KL-Pad11)") (class "Default")
      (node (ref "POWER") (pin "11") (pinfunction "KL_11") (pintype "passive"))
    )
    (net (code "75") (name "unconnected-(POWERD-KL-Pad12)") (class "Default")
      (node (ref "POWER") (pin "12") (pinfunction "KL_12") (pintype "passive"))
    )
    (net (code "76") (name "unconnected-(POWERE-KL-Pad13)") (class "Default")
      (node (ref "POWER") (pin "13") (pinfunction "KL_13") (pintype "passive"))
    )
    (net (code "77") (name "unconnected-(POWERF-KL-Pad14)") (class "Default")
      (node (ref "POWER") (pin "14") (pinfunction "KL_14") (pintype "passive"))
    )
    (net (code "78") (name "unconnected-(POWERG-KL-Pad15)") (class "Default")
      (node (ref "POWER") (pin "15") (pinfunction "KL_15") (pintype "passive"))
    )
    (net (code "79") (name "unconnected-(POWERH-KL-Pad16)") (class "Default")
      (node (ref "POWER") (pin "16") (pinfunction "KL_16") (pintype "passive"))
    )
    (net (code "80") (name "unconnected-(S1-O-Pad1)") (class "Default")
      (node (ref "S1") (pin "1") (pinfunction "O_1") (pintype "passive"))
    )
  )
)
